# untitled.net
KiCad netlist of a schematic drawn in EAGLE
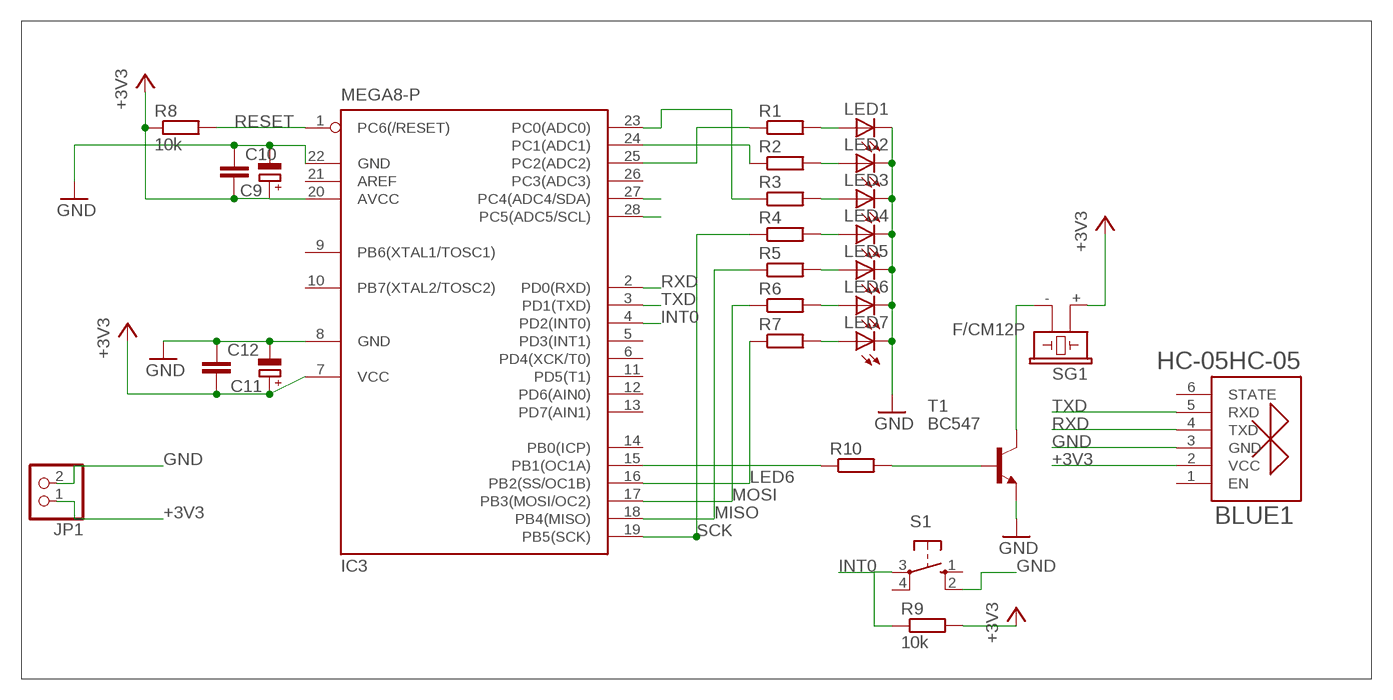
[diagram p0: schematic, sheet 1]

(export (version "E")
  (design (tool "Eeschema 10.0.6"))
  (components
    (comp (ref "BLUE1")
      (value "HC-05HC-05")
      (footprint "eagle-import:HC-05")
      (libsource (lib "eagle-import") (part "HC-05HC-05"))
    )
    (comp (ref "C9")
      (value "CPOL-EUE1.8-4")
      (footprint "eagle-import:E1,8-4")
      (libsource (lib "eagle-import") (part "CPOL-EUE1.8-4"))
    )
    (comp (ref "C10")
      (value "C-EU025-024X044")
      (footprint "eagle-import:C025-024X044")
      (libsource (lib "eagle-import") (part "C-EU025-024X044"))
    )
    (comp (ref "C11")
      (value "CPOL-EUE1.8-4")
      (footprint "eagle-import:E1,8-4")
      (libsource (lib "eagle-import") (part "CPOL-EUE1.8-4"))
    )
    (comp (ref "C12")
      (value "C-EU025-024X044")
      (footprint "eagle-import:C025-024X044")
      (libsource (lib "eagle-import") (part "C-EU025-024X044"))
    )
    (comp (ref "IC3")
      (value "MEGA8-P")
      (footprint "eagle-import:DIL28-3")
      (libsource (lib "eagle-import") (part "MEGA8-P"))
    )
    (comp (ref "JP1")
      (value "PINHD-1X2")
      (footprint "eagle-import:1X02")
      (libsource (lib "eagle-import") (part "PINHD-1X2"))
    )
    (comp (ref "LED1")
      (value "LED5MM")
      (footprint "eagle-import:LED5MM")
      (libsource (lib "eagle-import") (part "LED5MM"))
    )
    (comp (ref "LED2")
      (value "LED5MM")
      (footprint "eagle-import:LED5MM")
      (libsource (lib "eagle-import") (part "LED5MM"))
    )
    (comp (ref "LED3")
      (value "LED5MM")
      (footprint "eagle-import:LED5MM")
      (libsource (lib "eagle-import") (part "LED5MM"))
    )
    (comp (ref "LED4")
      (value "LED5MM")
      (footprint "eagle-import:LED5MM")
      (libsource (lib "eagle-import") (part "LED5MM"))
    )
    (comp (ref "LED5")
      (value "LED5MM")
      (footprint "eagle-import:LED5MM")
      (libsource (lib "eagle-import") (part "LED5MM"))
    )
    (comp (ref "LED6")
      (value "LED5MM")
      (footprint "eagle-import:LED5MM")
      (libsource (lib "eagle-import") (part "LED5MM"))
    )
    (comp (ref "LED7")
      (value "LED5MM")
      (footprint "eagle-import:LED5MM")
      (libsource (lib "eagle-import") (part "LED5MM"))
    )
    (comp (ref "R1")
      (value "R-EU_0204/7")
      (footprint "eagle-import:0204_7")
      (libsource (lib "eagle-import") (part "R-EU_0204/7"))
    )
    (comp (ref "R2")
      (value "R-EU_0204/7")
      (footprint "eagle-import:0204_7")
      (libsource (lib "eagle-import") (part "R-EU_0204/7"))
    )
    (comp (ref "R3")
      (value "R-EU_0204/7")
      (footprint "eagle-import:0204_7")
      (libsource (lib "eagle-import") (part "R-EU_0204/7"))
    )
    (comp (ref "R4")
      (value "R-EU_0204/7")
      (footprint "eagle-import:0204_7")
      (libsource (lib "eagle-import") (part "R-EU_0204/7"))
    )
    (comp (ref "R5")
      (value "R-EU_0204/7")
      (footprint "eagle-import:0204_7")
      (libsource (lib "eagle-import") (part "R-EU_0204/7"))
    )
    (comp (ref "R6")
      (value "R-EU_0204/7")
      (footprint "eagle-import:0204_7")
      (libsource (lib "eagle-import") (part "R-EU_0204/7"))
    )
    (comp (ref "R7")
      (value "R-EU_0204/7")
      (footprint "eagle-import:0204_7")
      (libsource (lib "eagle-import") (part "R-EU_0204/7"))
    )
    (comp (ref "R8")
      (value "10k")
      (footprint "eagle-import:0204_7")
      (libsource (lib "eagle-import") (part "R-EU_0204/7"))
    )
    (comp (ref "R9")
      (value "10k")
      (footprint "eagle-import:0207_10")
      (libsource (lib "eagle-import") (part "R-EU_0207/10"))
    )
    (comp (ref "R10")
      (value "R-EU_0204/7")
      (footprint "eagle-import:0204_7")
      (libsource (lib "eagle-import") (part "R-EU_0204/7"))
    )
    (comp (ref "S1")
      (value "10-XX")
      (footprint "eagle-import:B3F-10XX")
      (fields (field (name "MPN") "B3F-1000"))
      (libsource (lib "eagle-import") (part "10-XX"))
    )
    (comp (ref "SG1")
      (value "F/CM12P")
      (footprint "eagle-import:F_CM12P")
      (libsource (lib "eagle-import") (part "F/CM12P"))
    )
    (comp (ref "T1")
      (value "BC547")
      (footprint "eagle-import:TO92")
      (libsource (lib "eagle-import") (part "BC547"))
    )
  )
  (nets
    (net (code "1") (name "+3V3") (class "Default")
      (node (ref "BLUE1") (pin "2") (pinfunction "VCC_2") (pintype "bidirectional"))
      (node (ref "C10") (pin "2") (pinfunction "2_2") (pintype "passive"))
      (node (ref "C11") (pin "+") (pinfunction "+_+") (pintype "passive"))
      (node (ref "C12") (pin "2") (pinfunction "2_2") (pintype "passive"))
      (node (ref "C9") (pin "+") (pinfunction "+_+") (pintype "passive"))
      (node (ref "IC3") (pin "20") (pinfunction "AVCC_20") (pintype "power_in"))
      (node (ref "IC3") (pin "7") (pinfunction "VCC_7") (pintype "power_in"))
      (node (ref "JP1") (pin "1") (pinfunction "1_1") (pintype "passive"))
      (node (ref "R8") (pin "1") (pinfunction "1_1") (pintype "passive"))
      (node (ref "R9") (pin "2") (pinfunction "2_2") (pintype "passive"))
      (node (ref "SG1") (pin "+") (pinfunction "1_+") (pintype "passive"))
    )
    (net (code "2") (name "/INT0") (class "Default")
      (node (ref "IC3") (pin "4") (pinfunction "PD2(INT0)_4") (pintype "bidirectional"))
      (node (ref "R9") (pin "1") (pinfunction "1_1") (pintype "passive"))
      (node (ref "S1") (pin "3") (pinfunction "P_3") (pintype "passive"))
    )
    (net (code "3") (name "/LED6") (class "Default")
      (node (ref "IC3") (pin "16") (pinfunction "PB2(SS/OC1B)_16") (pintype "bidirectional"))
      (node (ref "R7") (pin "1") (pinfunction "1_1") (pintype "passive"))
    )
    (net (code "4") (name "/MISO") (class "Default")
      (node (ref "IC3") (pin "18") (pinfunction "PB4(MISO)_18") (pintype "bidirectional"))
      (node (ref "R5") (pin "1") (pinfunction "1_1") (pintype "passive"))
    )
    (net (code "5") (name "/MOSI") (class "Default")
      (node (ref "IC3") (pin "17") (pinfunction "PB3(MOSI/OC2)_17") (pintype "bidirectional"))
      (node (ref "R6") (pin "1") (pinfunction "1_1") (pintype "passive"))
    )
    (net (code "6") (name "/RESET") (class "Default")
      (node (ref "IC3") (pin "1") (pinfunction "PC6(/RESET)_1") (pintype "bidirectional"))
      (node (ref "R8") (pin "2") (pinfunction "2_2") (pintype "passive"))
    )
    (net (code "7") (name "/RXD") (class "Default")
      (node (ref "BLUE1") (pin "4") (pinfunction "TXD_4") (pintype "bidirectional"))
      (node (ref "IC3") (pin "2") (pinfunction "PD0(RXD)_2") (pintype "bidirectional"))
    )
    (net (code "8") (name "/SCK") (class "Default")
      (node (ref "IC3") (pin "19") (pinfunction "PB5(SCK)_19") (pintype "bidirectional"))
      (node (ref "R4") (pin "1") (pinfunction "1_1") (pintype "passive"))
    )
    (net (code "9") (name "/TXD") (class "Default")
      (node (ref "BLUE1") (pin "5") (pinfunction "RXD_5") (pintype "bidirectional"))
      (node (ref "IC3") (pin "3") (pinfunction "PD1(TXD)_3") (pintype "bidirectional"))
    )
    (net (code "10") (name "GND") (class "Default")
      (node (ref "BLUE1") (pin "3") (pinfunction "GND_3") (pintype "bidirectional"))
      (node (ref "C10") (pin "1") (pinfunction "1_1") (pintype "passive"))
      (node (ref "C11") (pin "-") (pinfunction "-_-") (pintype "passive"))
      (node (ref "C12") (pin "1") (pinfunction "1_1") (pintype "passive"))
      (node (ref "C9") (pin "-") (pinfunction "-_-") (pintype "passive"))
      (node (ref "IC3") (pin "22") (pinfunction "GND_22") (pintype "power_in"))
      (node (ref "IC3") (pin "8") (pinfunction "GND_8") (pintype "power_in"))
      (node (ref "JP1") (pin "2") (pinfunction "2_2") (pintype "passive"))
      (node (ref "LED1") (pin "K") (pinfunction "C_K") (pintype "passive"))
      (node (ref "LED2") (pin "K") (pinfunction "C_K") (pintype "passive"))
      (node (ref "LED3") (pin "K") (pinfunction "C_K") (pintype "passive"))
      (node (ref "LED4") (pin "K") (pinfunction "C_K") (pintype "passive"))
      (node (ref "LED5") (pin "K") (pinfunction "C_K") (pintype "passive"))
      (node (ref "LED6") (pin "K") (pinfunction "C_K") (pintype "passive"))
      (node (ref "LED7") (pin "K") (pinfunction "C_K") (pintype "passive"))
      (node (ref "S1") (pin "2") (pinfunction "S1_2") (pintype "passive"))
      (node (ref "T1") (pin "1") (pinfunction "E_1") (pintype "passive"))
    )
    (net (code "11") (name "Net-(IC3-PB1(OC1A))") (class "Default")
      (node (ref "IC3") (pin "15") (pinfunction "PB1(OC1A)_15") (pintype "bidirectional"))
      (node (ref "R10") (pin "1") (pinfunction "1_1") (pintype "passive"))
    )
    (net (code "12") (name "Net-(IC3-PC0(ADC0))") (class "Default")
      (node (ref "IC3") (pin "23") (pinfunction "PC0(ADC0)_23") (pintype "bidirectional"))
      (node (ref "R3") (pin "1") (pinfunction "1_1") (pintype "passive"))
    )
    (net (code "13") (name "Net-(IC3-PC1(ADC1))") (class "Default")
      (node (ref "IC3") (pin "24") (pinfunction "PC1(ADC1)_24") (pintype "bidirectional"))
      (node (ref "R2") (pin "1") (pinfunction "1_1") (pintype "passive"))
    )
    (net (code "14") (name "Net-(IC3-PC2(ADC2))") (class "Default")
      (node (ref "IC3") (pin "25") (pinfunction "PC2(ADC2)_25") (pintype "bidirectional"))
      (node (ref "R1") (pin "1") (pinfunction "1_1") (pintype "passive"))
    )
    (net (code "15") (name "Net-(LED1-PadA)") (class "Default")
      (node (ref "LED1") (pin "A") (pinfunction "A_A") (pintype "passive"))
      (node (ref "R1") (pin "2") (pinfunction "2_2") (pintype "passive"))
    )
    (net (code "16") (name "Net-(LED2-PadA)") (class "Default")
      (node (ref "LED2") (pin "A") (pinfunction "A_A") (pintype "passive"))
      (node (ref "R2") (pin "2") (pinfunction "2_2") (pintype "passive"))
    )
    (net (code "17") (name "Net-(LED3-PadA)") (class "Default")
      (node (ref "LED3") (pin "A") (pinfunction "A_A") (pintype "passive"))
      (node (ref "R3") (pin "2") (pinfunction "2_2") (pintype "passive"))
    )
    (net (code "18") (name "Net-(LED4-PadA)") (class "Default")
      (node (ref "LED4") (pin "A") (pinfunction "A_A") (pintype "passive"))
      (node (ref "R4") (pin "2") (pinfunction "2_2") (pintype "passive"))
    )
    (net (code "19") (name "Net-(LED5-PadA)") (class "Default")
      (node (ref "LED5") (pin "A") (pinfunction "A_A") (pintype "passive"))
      (node (ref "R5") (pin "2") (pinfunction "2_2") (pintype "passive"))
    )
    (net (code "20") (name "Net-(LED6-PadA)") (class "Default")
      (node (ref "LED6") (pin "A") (pinfunction "A_A") (pintype "passive"))
      (node (ref "R6") (pin "2") (pinfunction "2_2") (pintype "passive"))
    )
    (net (code "21") (name "Net-(LED7-PadA)") (class "Default")
      (node (ref "LED7") (pin "A") (pinfunction "A_A") (pintype "passive"))
      (node (ref "R7") (pin "2") (pinfunction "2_2") (pintype "passive"))
    )
    (net (code "22") (name "Net-(SG1-2)") (class "Default")
      (node (ref "SG1") (pin "-") (pinfunction "2_-") (pintype "passive"))
      (node (ref "T1") (pin "3") (pinfunction "C_3") (pintype "passive"))
    )
    (net (code "23") (name "Net-(T1-B)") (class "Default")
      (node (ref "R10") (pin "2") (pinfunction "2_2") (pintype "passive"))
      (node (ref "T1") (pin "2") (pinfunction "B_2") (pintype "passive"))
    )
    (net (code "24") (name "unconnected-(BLUE1-EN-Pad1)") (class "Default")
      (node (ref "BLUE1") (pin "1") (pinfunction "EN_1") (pintype "bidirectional"))
    )
    (net (code "25") (name "unconnected-(BLUE1-STATE-Pad6)") (class "Default")
      (node (ref "BLUE1") (pin "6") (pinfunction "STATE_6") (pintype "bidirectional"))
    )
    (net (code "26") (name "unconnected-(IC3-AREF-Pad21)") (class "Default")
      (node (ref "IC3") (pin "21") (pinfunction "AREF_21") (pintype "passive"))
    )
    (net (code "27") (name "unconnected-(IC3-PB0(ICP)-Pad14)") (class "Default")
      (node (ref "IC3") (pin "14") (pinfunction "PB0(ICP)_14") (pintype "bidirectional"))
    )
    (net (code "28") (name "unconnected-(IC3-PB6(XTAL1{slash}TOSC1)-Pad9)") (class "Default")
      (node (ref "IC3") (pin "9") (pinfunction "PB6(XTAL1/TOSC1)_9") (pintype "bidirectional"))
    )
    (net (code "29") (name "unconnected-(IC3-PB7(XTAL2{slash}TOSC2)-Pad10)") (class "Default")
      (node (ref "IC3") (pin "10") (pinfunction "PB7(XTAL2/TOSC2)_10") (pintype "bidirectional"))
    )
    (net (code "30") (name "unconnected-(IC3-PC3(ADC3)-Pad26)") (class "Default")
      (node (ref "IC3") (pin "26") (pinfunction "PC3(ADC3)_26") (pintype "bidirectional"))
    )
    (net (code "31") (name "unconnected-(IC3-PC4(ADC4{slash}SDA)-Pad27)") (class "Default")
      (node (ref "IC3") (pin "27") (pinfunction "PC4(ADC4/SDA)_27") (pintype "bidirectional"))
    )
    (net (code "32") (name "unconnected-(IC3-PC5(ADC5{slash}SCL)-Pad28)") (class "Default")
      (node (ref "IC3") (pin "28") (pinfunction "PC5(ADC5/SCL)_28") (pintype "bidirectional"))
    )
    (net (code "33") (name "unconnected-(IC3-PD3(INT1)-Pad5)") (class "Default")
      (node (ref "IC3") (pin "5") (pinfunction "PD3(INT1)_5") (pintype "bidirectional"))
    )
    (net (code "34") (name "unconnected-(IC3-PD4(XCK{slash}T0)-Pad6)") (class "Default")
      (node (ref "IC3") (pin "6") (pinfunction "PD4(XCK/T0)_6") (pintype "bidirectional"))
    )
    (net (code "35") (name "unconnected-(IC3-PD5(T1)-Pad11)") (class "Default")
      (node (ref "IC3") (pin "11") (pinfunction "PD5(T1)_11") (pintype "bidirectional"))
    )
    (net (code "36") (name "unconnected-(IC3-PD6(AIN0)-Pad12)") (class "Default")
      (node (ref "IC3") (pin "12") (pinfunction "PD6(AIN0)_12") (pintype "bidirectional"))
    )
    (net (code "37") (name "unconnected-(IC3-PD7(AIN1)-Pad13)") (class "Default")
      (node (ref "IC3") (pin "13") (pinfunction "PD7(AIN1)_13") (pintype "bidirectional"))
    )
    (net (code "38") (name "unconnected-(S1-P1-Pad4)") (class "Default")
      (node (ref "S1") (pin "4") (pinfunction "P1_4") (pintype "passive"))
    )
    (net (code "39") (name "unconnected-(S1-S-Pad1)") (class "Default")
      (node (ref "S1") (pin "1") (pinfunction "S_1") (pintype "passive"))
    )
  )
)
